# Radio_Board.net
KiCad netlist of a schematic drawn in EAGLE
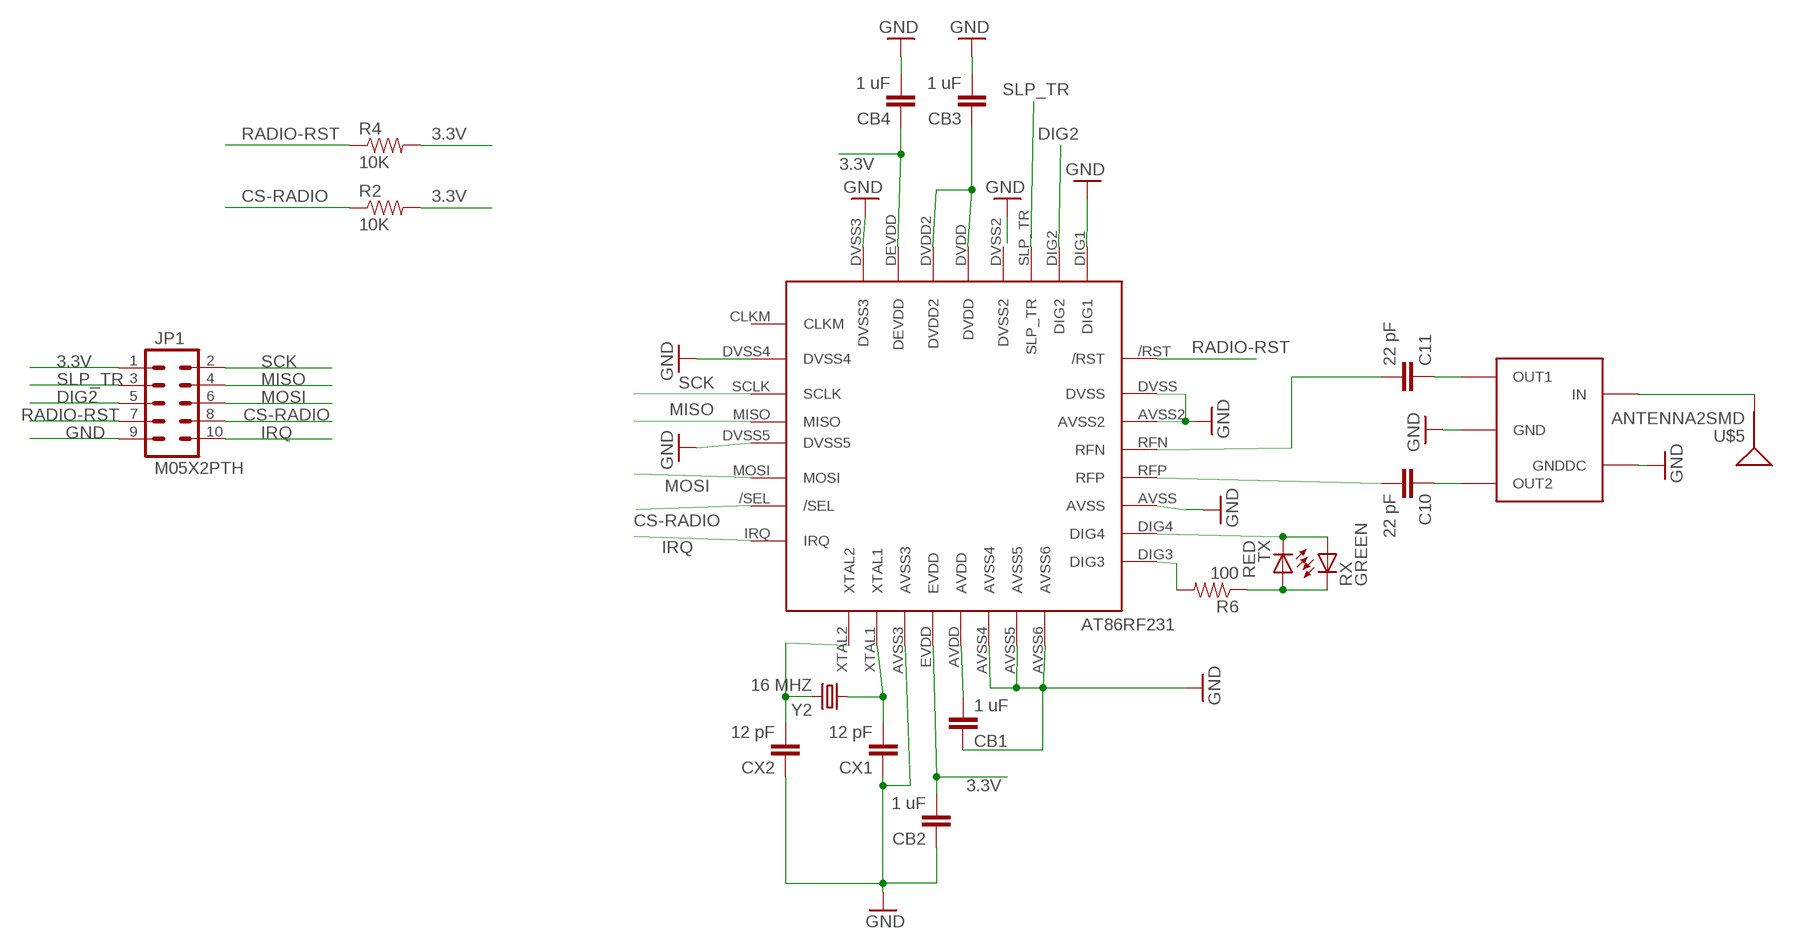
[diagram p0: schematic, sheet 1]

(export (version "E")
  (design (tool "Eeschema 10.0.6"))
  (components
    (comp (ref "C10")
      (value "22 pF")
      (footprint "eagle-import:0603-CAP")
      (libsource (lib "eagle-import") (part "CAP0603-CAP"))
    )
    (comp (ref "C11")
      (value "22 pF")
      (footprint "eagle-import:0603-CAP")
      (libsource (lib "eagle-import") (part "CAP0603-CAP"))
    )
    (comp (ref "CB1")
      (value "1 uF")
      (footprint "eagle-import:0603-CAP")
      (libsource (lib "eagle-import") (part "CAP0603-CAP"))
    )
    (comp (ref "CB2")
      (value "1 uF")
      (footprint "eagle-import:0603-CAP")
      (libsource (lib "eagle-import") (part "CAP0603-CAP"))
    )
    (comp (ref "CB3")
      (value "1 uF")
      (footprint "eagle-import:0603-CAP")
      (libsource (lib "eagle-import") (part "CAP0603-CAP"))
    )
    (comp (ref "CB4")
      (value "1 uF")
      (footprint "eagle-import:0603-CAP")
      (libsource (lib "eagle-import") (part "CAP0603-CAP"))
    )
    (comp (ref "CX1")
      (value "12 pF")
      (footprint "eagle-import:0603-CAP")
      (libsource (lib "eagle-import") (part "CAP0603-CAP"))
    )
    (comp (ref "CX2")
      (value "12 pF")
      (footprint "eagle-import:0603-CAP")
      (libsource (lib "eagle-import") (part "CAP0603-CAP"))
    )
    (comp (ref "JP1")
      (value "M05X2PTH")
      (footprint "eagle-import:AVR_ICSP")
      (libsource (lib "eagle-import") (part "M05X2PTH"))
    )
    (comp (ref "R2")
      (value "10K")
      (footprint "eagle-import:0603-RES")
      (libsource (lib "eagle-import") (part "RESISTOR0603-RES"))
    )
    (comp (ref "R4")
      (value "10K")
      (footprint "eagle-import:0603-RES")
      (libsource (lib "eagle-import") (part "RESISTOR0603-RES"))
    )
    (comp (ref "R6")
      (value "100")
      (footprint "eagle-import:0603-RES")
      (libsource (lib "eagle-import") (part "RESISTOR0603-RES"))
    )
    (comp (ref "RX")
      (value "GREEN")
      (footprint "eagle-import:LED-0603")
      (libsource (lib "eagle-import") (part "LED0603"))
    )
    (comp (ref "TX")
      (value "RED")
      (footprint "eagle-import:LED-0603")
      (libsource (lib "eagle-import") (part "LED0603"))
    )
    (comp (ref "U$3")
      (value "AT86RF231(RADIO)AT86RF231")
      (footprint "eagle-import:32QN2(RADIO)")
      (libsource (lib "eagle-import") (part "AT86RF231(RADIO)AT86RF231"))
    )
    (comp (ref "U$4")
      (value "WE-BAL")
      (footprint "eagle-import:WE-BAL")
      (libsource (lib "eagle-import") (part "WE-BAL"))
    )
    (comp (ref "U$5")
      (value "ANTENNA2SMD")
      (footprint "eagle-import:ANTENNA-CHIP2")
      (libsource (lib "eagle-import") (part "ANTENNA2SMD"))
    )
    (comp (ref "Y2")
      (value "16 MHZ")
      (footprint "eagle-import:HC49UP")
      (libsource (lib "eagle-import") (part "CRYSTALSMD"))
    )
  )
  (nets
    (net (code "1") (name "/3.3V") (class "Default")
      (node (ref "CB2") (pin "2") (pinfunction "2_2") (pintype "passive"))
      (node (ref "CB4") (pin "1") (pinfunction "1_1") (pintype "passive"))
      (node (ref "JP1") (pin "1") (pinfunction "1_1") (pintype "passive"))
      (node (ref "R2") (pin "2") (pinfunction "2_2") (pintype "passive"))
      (node (ref "R4") (pin "2") (pinfunction "2_2") (pintype "passive"))
      (node (ref "U$3") (pin "DEVDD") (pinfunction "DEVDD_DEVDD") (pintype "bidirectional"))
      (node (ref "U$3") (pin "EVDD") (pinfunction "EVDD_EVDD") (pintype "bidirectional"))
    )
    (net (code "2") (name "/CS-RADIO") (class "Default")
      (node (ref "JP1") (pin "8") (pinfunction "8_8") (pintype "passive"))
      (node (ref "R2") (pin "1") (pinfunction "1_1") (pintype "passive"))
      (node (ref "U$3") (pin "/SEL") (pinfunction "/SEL_/SEL") (pintype "bidirectional"))
    )
    (net (code "3") (name "/DIG2") (class "Default")
      (node (ref "JP1") (pin "5") (pinfunction "5_5") (pintype "passive"))
      (node (ref "U$3") (pin "DIG2") (pinfunction "DIG2_DIG2") (pintype "bidirectional"))
    )
    (net (code "4") (name "/IRQ") (class "Default")
      (node (ref "JP1") (pin "10") (pinfunction "10_10") (pintype "passive"))
      (node (ref "U$3") (pin "IRQ") (pinfunction "IRQ_IRQ") (pintype "bidirectional"))
    )
    (net (code "5") (name "/MISO") (class "Default")
      (node (ref "JP1") (pin "4") (pinfunction "4_4") (pintype "passive"))
      (node (ref "U$3") (pin "MISO") (pinfunction "MISO_MISO") (pintype "bidirectional"))
    )
    (net (code "6") (name "/MOSI") (class "Default")
      (node (ref "JP1") (pin "6") (pinfunction "6_6") (pintype "passive"))
      (node (ref "U$3") (pin "MOSI") (pinfunction "MOSI_MOSI") (pintype "bidirectional"))
    )
    (net (code "7") (name "/RADIO-RST") (class "Default")
      (node (ref "JP1") (pin "7") (pinfunction "7_7") (pintype "passive"))
      (node (ref "R4") (pin "1") (pinfunction "1_1") (pintype "passive"))
      (node (ref "U$3") (pin "/RST") (pinfunction "/RST_/RST") (pintype "bidirectional"))
    )
    (net (code "8") (name "/SCK") (class "Default")
      (node (ref "JP1") (pin "2") (pinfunction "2_2") (pintype "passive"))
      (node (ref "U$3") (pin "SCLK") (pinfunction "SCLK_SCLK") (pintype "bidirectional"))
    )
    (net (code "9") (name "/SLP_TR") (class "Default")
      (node (ref "JP1") (pin "3") (pinfunction "3_3") (pintype "passive"))
      (node (ref "U$3") (pin "SLP_TR") (pinfunction "SLP_TR_SLP_TR") (pintype "bidirectional"))
    )
    (net (code "10") (name "GND") (class "Default")
      (node (ref "CB1") (pin "1") (pinfunction "1_1") (pintype "passive"))
      (node (ref "CB2") (pin "1") (pinfunction "1_1") (pintype "passive"))
      (node (ref "CB3") (pin "2") (pinfunction "2_2") (pintype "passive"))
      (node (ref "CB4") (pin "2") (pinfunction "2_2") (pintype "passive"))
      (node (ref "CX1") (pin "1") (pinfunction "1_1") (pintype "passive"))
      (node (ref "CX2") (pin "1") (pinfunction "1_1") (pintype "passive"))
      (node (ref "JP1") (pin "9") (pinfunction "9_9") (pintype "passive"))
      (node (ref "U$3") (pin "AVSS") (pinfunction "AVSS_AVSS") (pintype "bidirectional"))
      (node (ref "U$3") (pin "AVSS2") (pinfunction "AVSS2_AVSS2") (pintype "bidirectional"))
      (node (ref "U$3") (pin "AVSS3") (pinfunction "AVSS3_AVSS3") (pintype "bidirectional"))
      (node (ref "U$3") (pin "AVSS4") (pinfunction "AVSS4_AVSS4") (pintype "bidirectional"))
      (node (ref "U$3") (pin "AVSS5") (pinfunction "AVSS5_AVSS5") (pintype "bidirectional"))
      (node (ref "U$3") (pin "AVSS6") (pinfunction "AVSS6_AVSS6") (pintype "bidirectional"))
      (node (ref "U$3") (pin "DIG1") (pinfunction "DIG1_DIG1") (pintype "bidirectional"))
      (node (ref "U$3") (pin "DVSS") (pinfunction "DVSS_DVSS") (pintype "bidirectional"))
      (node (ref "U$3") (pin "DVSS3") (pinfunction "DVSS3_DVSS3") (pintype "bidirectional"))
      (node (ref "U$3") (pin "DVSS4") (pinfunction "DVSS4_DVSS4") (pintype "bidirectional"))
      (node (ref "U$3") (pin "DVSS5") (pinfunction "DVSS5_DVSS5") (pintype "bidirectional"))
      (node (ref "U$4") (pin "GND") (pinfunction "GND_GND") (pintype "bidirectional"))
      (node (ref "U$4") (pin "GNDDC") (pinfunction "GNDDC_GNDDC") (pintype "bidirectional"))
    )
    (net (code "11") (name "Net-(C10-Pad1)") (class "Default")
      (node (ref "C10") (pin "1") (pinfunction "1_1") (pintype "passive"))
      (node (ref "U$4") (pin "OUT2") (pinfunction "OUT2_OUT2") (pintype "bidirectional"))
    )
    (net (code "12") (name "Net-(C10-Pad2)") (class "Default")
      (node (ref "C10") (pin "2") (pinfunction "2_2") (pintype "passive"))
      (node (ref "U$3") (pin "RFP") (pinfunction "RFP_RFP") (pintype "bidirectional"))
    )
    (net (code "13") (name "Net-(C11-Pad1)") (class "Default")
      (node (ref "C11") (pin "1") (pinfunction "1_1") (pintype "passive"))
      (node (ref "U$4") (pin "OUT1") (pinfunction "OUT1_OUT1") (pintype "bidirectional"))
    )
    (net (code "14") (name "Net-(C11-Pad2)") (class "Default")
      (node (ref "C11") (pin "2") (pinfunction "2_2") (pintype "passive"))
      (node (ref "U$3") (pin "RFN") (pinfunction "RFN_RFN") (pintype "bidirectional"))
    )
    (net (code "15") (name "Net-(CB1-Pad2)") (class "Default")
      (node (ref "CB1") (pin "2") (pinfunction "2_2") (pintype "passive"))
      (node (ref "U$3") (pin "AVDD") (pinfunction "AVDD_AVDD") (pintype "bidirectional"))
    )
    (net (code "16") (name "Net-(CB3-Pad1)") (class "Default")
      (node (ref "CB3") (pin "1") (pinfunction "1_1") (pintype "passive"))
      (node (ref "U$3") (pin "DVDD") (pinfunction "DVDD_DVDD") (pintype "bidirectional"))
      (node (ref "U$3") (pin "DVDD2") (pinfunction "DVDD2_DVDD2") (pintype "bidirectional"))
    )
    (net (code "17") (name "Net-(CX1-Pad2)") (class "Default")
      (node (ref "CX1") (pin "2") (pinfunction "2_2") (pintype "passive"))
      (node (ref "U$3") (pin "XTAL1") (pinfunction "XTAL1_XTAL1") (pintype "bidirectional"))
      (node (ref "Y2") (pin "1") (pinfunction "1_1") (pintype "passive"))
    )
    (net (code "18") (name "Net-(CX2-Pad2)") (class "Default")
      (node (ref "CX2") (pin "2") (pinfunction "2_2") (pintype "passive"))
      (node (ref "U$3") (pin "XTAL2") (pinfunction "XTAL2_XTAL2") (pintype "bidirectional"))
      (node (ref "Y2") (pin "2") (pinfunction "2_2") (pintype "passive"))
    )
    (net (code "19") (name "Net-(R6-Pad1)") (class "Default")
      (node (ref "R6") (pin "1") (pinfunction "1_1") (pintype "passive"))
      (node (ref "RX") (pin "C") (pinfunction "C_C") (pintype "passive"))
      (node (ref "TX") (pin "A") (pinfunction "A_A") (pintype "passive"))
    )
    (net (code "20") (name "Net-(R6-Pad2)") (class "Default")
      (node (ref "R6") (pin "2") (pinfunction "2_2") (pintype "passive"))
      (node (ref "U$3") (pin "DIG3") (pinfunction "DIG3_DIG3") (pintype "bidirectional"))
    )
    (net (code "21") (name "Net-(RX-PadA)") (class "Default")
      (node (ref "RX") (pin "A") (pinfunction "A_A") (pintype "passive"))
      (node (ref "TX") (pin "C") (pinfunction "C_C") (pintype "passive"))
      (node (ref "U$3") (pin "DIG4") (pinfunction "DIG4_DIG4") (pintype "bidirectional"))
    )
    (net (code "22") (name "Net-(U$5-SIGNAL)") (class "Default")
      (node (ref "U$4") (pin "IN") (pinfunction "IN_IN") (pintype "bidirectional"))
      (node (ref "U$5") (pin "FEED") (pinfunction "SIGNAL_FEED") (pintype "bidirectional"))
    )
    (net (code "23") (name "unconnected-(U$3-PadCLKM)") (class "Default")
      (node (ref "U$3") (pin "CLKM") (pinfunction "CLKM_CLKM") (pintype "bidirectional"))
    )
    (net (code "24") (name "unconnected-(U$3-PadDVSS2)") (class "Default")
      (node (ref "U$3") (pin "DVSS2") (pinfunction "DVSS2_DVSS2") (pintype "bidirectional"))
    )
  )
)
